# input5.net
KiCad netlist of a schematic drawn in Altium Designer
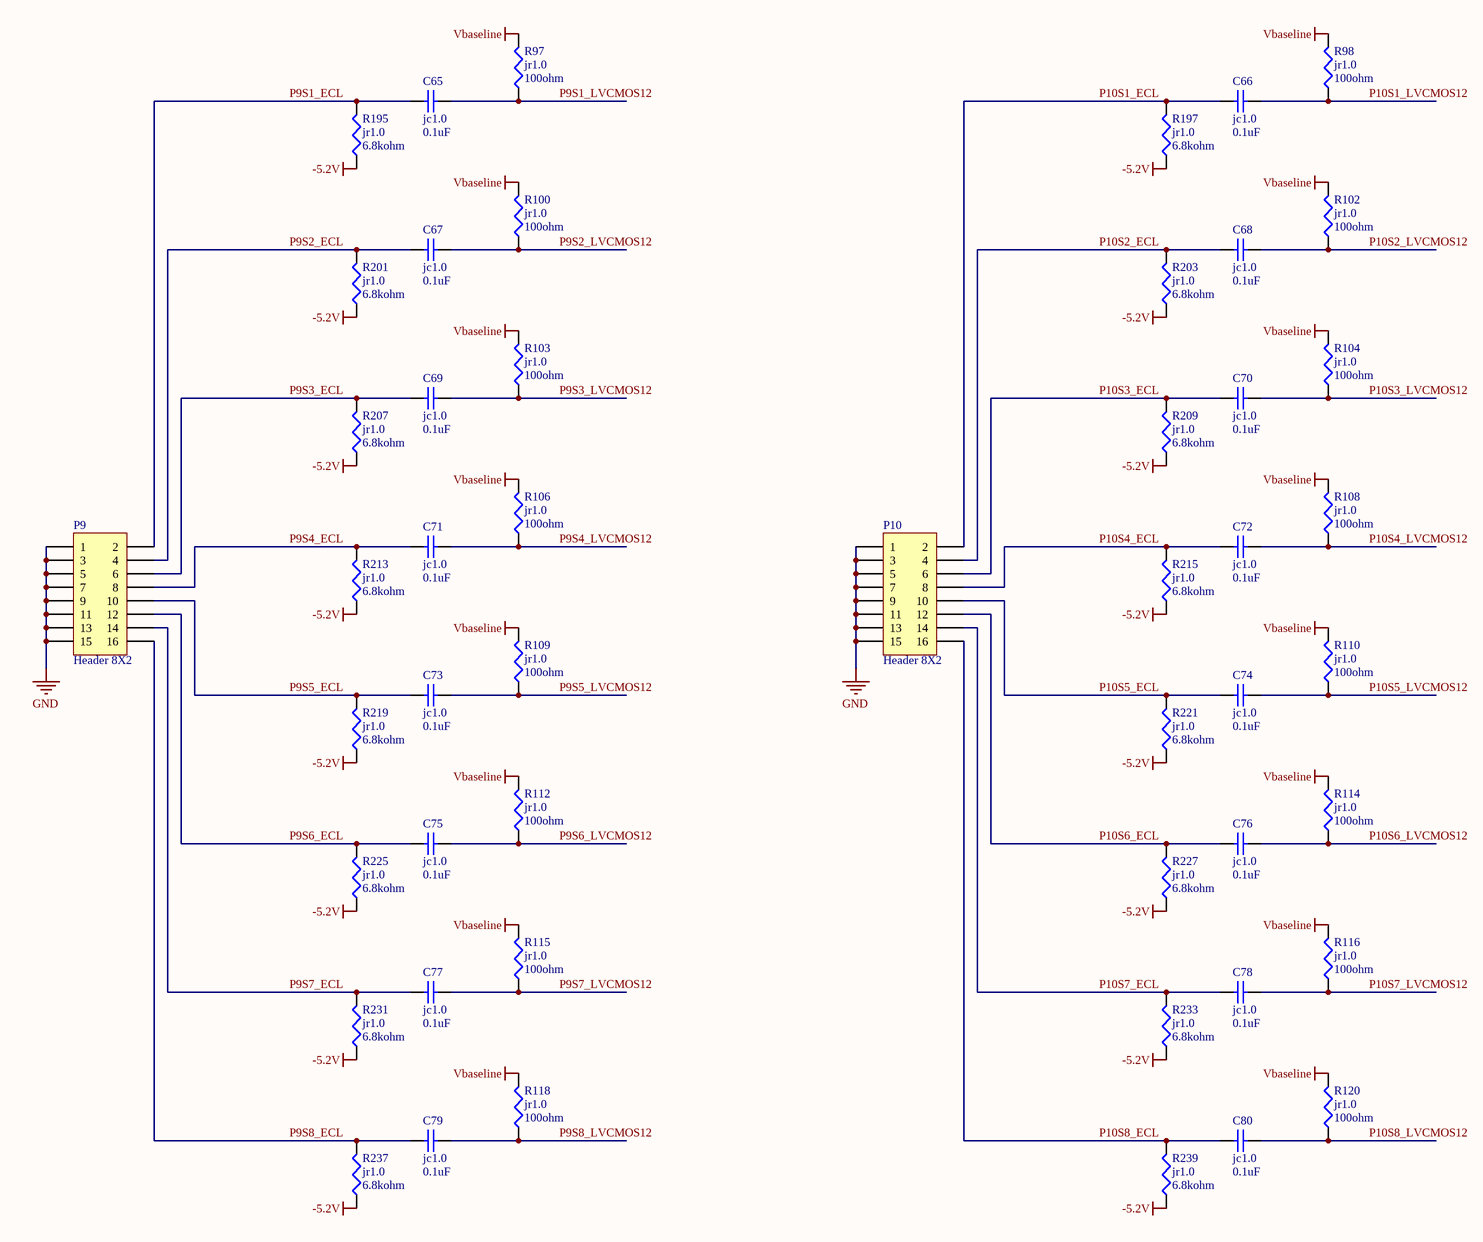
[diagram p0: input5.SchDoc]

(export (version "E")
  (design (tool "Eeschema 10.0.6"))
  (components
    (comp (ref "C65")
      (value "jc1.0")
      (footprint "0402")
      (description "Capacitor")
      (fields (field (name "ALTIUM_VALUE") "0.1uF") (field (name "PUBLISHER") "Altium Limited"))
      (libsource (lib "LIB01DXP2006SchLib") (part "Cap"))
    )
    (comp (ref "C66")
      (value "jc1.0")
      (footprint "0402")
      (description "Capacitor")
      (fields (field (name "ALTIUM_VALUE") "0.1uF") (field (name "PUBLISHER") "Altium Limited"))
      (libsource (lib "LIB01DXP2006SchLib") (part "Cap"))
    )
    (comp (ref "C67")
      (value "jc1.0")
      (footprint "0402")
      (description "Capacitor")
      (fields (field (name "ALTIUM_VALUE") "0.1uF") (field (name "PUBLISHER") "Altium Limited"))
      (libsource (lib "LIB01DXP2006SchLib") (part "Cap"))
    )
    (comp (ref "C68")
      (value "jc1.0")
      (footprint "0402")
      (description "Capacitor")
      (fields (field (name "ALTIUM_VALUE") "0.1uF") (field (name "PUBLISHER") "Altium Limited"))
      (libsource (lib "LIB01DXP2006SchLib") (part "Cap"))
    )
    (comp (ref "C69")
      (value "jc1.0")
      (footprint "0402")
      (description "Capacitor")
      (fields (field (name "ALTIUM_VALUE") "0.1uF") (field (name "PUBLISHER") "Altium Limited"))
      (libsource (lib "LIB01DXP2006SchLib") (part "Cap"))
    )
    (comp (ref "C70")
      (value "jc1.0")
      (footprint "0402")
      (description "Capacitor")
      (fields (field (name "ALTIUM_VALUE") "0.1uF") (field (name "PUBLISHER") "Altium Limited"))
      (libsource (lib "LIB01DXP2006SchLib") (part "Cap"))
    )
    (comp (ref "C71")
      (value "jc1.0")
      (footprint "0402")
      (description "Capacitor")
      (fields (field (name "ALTIUM_VALUE") "0.1uF") (field (name "PUBLISHER") "Altium Limited"))
      (libsource (lib "LIB01DXP2006SchLib") (part "Cap"))
    )
    (comp (ref "C72")
      (value "jc1.0")
      (footprint "0402")
      (description "Capacitor")
      (fields (field (name "ALTIUM_VALUE") "0.1uF") (field (name "PUBLISHER") "Altium Limited"))
      (libsource (lib "LIB01DXP2006SchLib") (part "Cap"))
    )
    (comp (ref "C73")
      (value "jc1.0")
      (footprint "0402")
      (description "Capacitor")
      (fields (field (name "ALTIUM_VALUE") "0.1uF") (field (name "PUBLISHER") "Altium Limited"))
      (libsource (lib "LIB01DXP2006SchLib") (part "Cap"))
    )
    (comp (ref "C74")
      (value "jc1.0")
      (footprint "0402")
      (description "Capacitor")
      (fields (field (name "ALTIUM_VALUE") "0.1uF") (field (name "PUBLISHER") "Altium Limited"))
      (libsource (lib "LIB01DXP2006SchLib") (part "Cap"))
    )
    (comp (ref "C75")
      (value "jc1.0")
      (footprint "0402")
      (description "Capacitor")
      (fields (field (name "ALTIUM_VALUE") "0.1uF") (field (name "PUBLISHER") "Altium Limited"))
      (libsource (lib "LIB01DXP2006SchLib") (part "Cap"))
    )
    (comp (ref "C76")
      (value "jc1.0")
      (footprint "0402")
      (description "Capacitor")
      (fields (field (name "ALTIUM_VALUE") "0.1uF") (field (name "PUBLISHER") "Altium Limited"))
      (libsource (lib "LIB01DXP2006SchLib") (part "Cap"))
    )
    (comp (ref "C77")
      (value "jc1.0")
      (footprint "0402")
      (description "Capacitor")
      (fields (field (name "ALTIUM_VALUE") "0.1uF") (field (name "PUBLISHER") "Altium Limited"))
      (libsource (lib "LIB01DXP2006SchLib") (part "Cap"))
    )
    (comp (ref "C78")
      (value "jc1.0")
      (footprint "0402")
      (description "Capacitor")
      (fields (field (name "ALTIUM_VALUE") "0.1uF") (field (name "PUBLISHER") "Altium Limited"))
      (libsource (lib "LIB01DXP2006SchLib") (part "Cap"))
    )
    (comp (ref "C79")
      (value "jc1.0")
      (footprint "0402")
      (description "Capacitor")
      (fields (field (name "ALTIUM_VALUE") "0.1uF") (field (name "PUBLISHER") "Altium Limited"))
      (libsource (lib "LIB01DXP2006SchLib") (part "Cap"))
    )
    (comp (ref "C80")
      (value "jc1.0")
      (footprint "0402")
      (description "Capacitor")
      (fields (field (name "ALTIUM_VALUE") "0.1uF") (field (name "PUBLISHER") "Altium Limited"))
      (libsource (lib "LIB01DXP2006SchLib") (part "Cap"))
    )
    (comp (ref "P9")
      (value "Header 8X2")
      (footprint "HDR2X8")
      (description "Header, 8-Pin, Dual row")
      (fields (field (name "PUBLISHER") "Altium Limited"))
      (libsource (lib "Miscellaneous Connectors") (part "Header 8X2"))
    )
    (comp (ref "P10")
      (value "Header 8X2")
      (footprint "HDR2X8")
      (description "Header, 8-Pin, Dual row")
      (fields (field (name "PUBLISHER") "Altium Limited"))
      (libsource (lib "Miscellaneous Connectors") (part "Header 8X2"))
    )
    (comp (ref "R97")
      (value "jr1.0")
      (footprint "0402")
      (description "Resistor")
      (fields (field (name "ALTIUM_VALUE") "100ohm") (field (name "PUBLISHER") "Altium Limited"))
      (libsource (lib "LIB01DXP2006SchLib") (part "Res"))
    )
    (comp (ref "R98")
      (value "jr1.0")
      (footprint "0402")
      (description "Resistor")
      (fields (field (name "ALTIUM_VALUE") "100ohm") (field (name "PUBLISHER") "Altium Limited"))
      (libsource (lib "LIB01DXP2006SchLib") (part "Res"))
    )
    (comp (ref "R100")
      (value "jr1.0")
      (footprint "0402")
      (description "Resistor")
      (fields (field (name "ALTIUM_VALUE") "100ohm") (field (name "PUBLISHER") "Altium Limited"))
      (libsource (lib "LIB01DXP2006SchLib") (part "Res"))
    )
    (comp (ref "R102")
      (value "jr1.0")
      (footprint "0402")
      (description "Resistor")
      (fields (field (name "ALTIUM_VALUE") "100ohm") (field (name "PUBLISHER") "Altium Limited"))
      (libsource (lib "LIB01DXP2006SchLib") (part "Res"))
    )
    (comp (ref "R103")
      (value "jr1.0")
      (footprint "0402")
      (description "Resistor")
      (fields (field (name "ALTIUM_VALUE") "100ohm") (field (name "PUBLISHER") "Altium Limited"))
      (libsource (lib "LIB01DXP2006SchLib") (part "Res"))
    )
    (comp (ref "R104")
      (value "jr1.0")
      (footprint "0402")
      (description "Resistor")
      (fields (field (name "ALTIUM_VALUE") "100ohm") (field (name "PUBLISHER") "Altium Limited"))
      (libsource (lib "LIB01DXP2006SchLib") (part "Res"))
    )
    (comp (ref "R106")
      (value "jr1.0")
      (footprint "0402")
      (description "Resistor")
      (fields (field (name "ALTIUM_VALUE") "100ohm") (field (name "PUBLISHER") "Altium Limited"))
      (libsource (lib "LIB01DXP2006SchLib") (part "Res"))
    )
    (comp (ref "R108")
      (value "jr1.0")
      (footprint "0402")
      (description "Resistor")
      (fields (field (name "ALTIUM_VALUE") "100ohm") (field (name "PUBLISHER") "Altium Limited"))
      (libsource (lib "LIB01DXP2006SchLib") (part "Res"))
    )
    (comp (ref "R109")
      (value "jr1.0")
      (footprint "0402")
      (description "Resistor")
      (fields (field (name "ALTIUM_VALUE") "100ohm") (field (name "PUBLISHER") "Altium Limited"))
      (libsource (lib "LIB01DXP2006SchLib") (part "Res"))
    )
    (comp (ref "R110")
      (value "jr1.0")
      (footprint "0402")
      (description "Resistor")
      (fields (field (name "ALTIUM_VALUE") "100ohm") (field (name "PUBLISHER") "Altium Limited"))
      (libsource (lib "LIB01DXP2006SchLib") (part "Res"))
    )
    (comp (ref "R112")
      (value "jr1.0")
      (footprint "0402")
      (description "Resistor")
      (fields (field (name "ALTIUM_VALUE") "100ohm") (field (name "PUBLISHER") "Altium Limited"))
      (libsource (lib "LIB01DXP2006SchLib") (part "Res"))
    )
    (comp (ref "R114")
      (value "jr1.0")
      (footprint "0402")
      (description "Resistor")
      (fields (field (name "ALTIUM_VALUE") "100ohm") (field (name "PUBLISHER") "Altium Limited"))
      (libsource (lib "LIB01DXP2006SchLib") (part "Res"))
    )
    (comp (ref "R115")
      (value "jr1.0")
      (footprint "0402")
      (description "Resistor")
      (fields (field (name "ALTIUM_VALUE") "100ohm") (field (name "PUBLISHER") "Altium Limited"))
      (libsource (lib "LIB01DXP2006SchLib") (part "Res"))
    )
    (comp (ref "R116")
      (value "jr1.0")
      (footprint "0402")
      (description "Resistor")
      (fields (field (name "ALTIUM_VALUE") "100ohm") (field (name "PUBLISHER") "Altium Limited"))
      (libsource (lib "LIB01DXP2006SchLib") (part "Res"))
    )
    (comp (ref "R118")
      (value "jr1.0")
      (footprint "0402")
      (description "Resistor")
      (fields (field (name "ALTIUM_VALUE") "100ohm") (field (name "PUBLISHER") "Altium Limited"))
      (libsource (lib "LIB01DXP2006SchLib") (part "Res"))
    )
    (comp (ref "R120")
      (value "jr1.0")
      (footprint "0402")
      (description "Resistor")
      (fields (field (name "ALTIUM_VALUE") "100ohm") (field (name "PUBLISHER") "Altium Limited"))
      (libsource (lib "LIB01DXP2006SchLib") (part "Res"))
    )
    (comp (ref "R195")
      (value "jr1.0")
      (footprint "0402")
      (description "Resistor")
      (fields (field (name "ALTIUM_VALUE") "6.8kohm") (field (name "PUBLISHER") "Altium Limited"))
      (libsource (lib "LIB01DXP2006SchLib") (part "Res"))
    )
    (comp (ref "R197")
      (value "jr1.0")
      (footprint "0402")
      (description "Resistor")
      (fields (field (name "ALTIUM_VALUE") "6.8kohm") (field (name "PUBLISHER") "Altium Limited"))
      (libsource (lib "LIB01DXP2006SchLib") (part "Res"))
    )
    (comp (ref "R201")
      (value "jr1.0")
      (footprint "0402")
      (description "Resistor")
      (fields (field (name "ALTIUM_VALUE") "6.8kohm") (field (name "PUBLISHER") "Altium Limited"))
      (libsource (lib "LIB01DXP2006SchLib") (part "Res"))
    )
    (comp (ref "R203")
      (value "jr1.0")
      (footprint "0402")
      (description "Resistor")
      (fields (field (name "ALTIUM_VALUE") "6.8kohm") (field (name "PUBLISHER") "Altium Limited"))
      (libsource (lib "LIB01DXP2006SchLib") (part "Res"))
    )
    (comp (ref "R207")
      (value "jr1.0")
      (footprint "0402")
      (description "Resistor")
      (fields (field (name "ALTIUM_VALUE") "6.8kohm") (field (name "PUBLISHER") "Altium Limited"))
      (libsource (lib "LIB01DXP2006SchLib") (part "Res"))
    )
    (comp (ref "R209")
      (value "jr1.0")
      (footprint "0402")
      (description "Resistor")
      (fields (field (name "ALTIUM_VALUE") "6.8kohm") (field (name "PUBLISHER") "Altium Limited"))
      (libsource (lib "LIB01DXP2006SchLib") (part "Res"))
    )
    (comp (ref "R213")
      (value "jr1.0")
      (footprint "0402")
      (description "Resistor")
      (fields (field (name "ALTIUM_VALUE") "6.8kohm") (field (name "PUBLISHER") "Altium Limited"))
      (libsource (lib "LIB01DXP2006SchLib") (part "Res"))
    )
    (comp (ref "R215")
      (value "jr1.0")
      (footprint "0402")
      (description "Resistor")
      (fields (field (name "ALTIUM_VALUE") "6.8kohm") (field (name "PUBLISHER") "Altium Limited"))
      (libsource (lib "LIB01DXP2006SchLib") (part "Res"))
    )
    (comp (ref "R219")
      (value "jr1.0")
      (footprint "0402")
      (description "Resistor")
      (fields (field (name "ALTIUM_VALUE") "6.8kohm") (field (name "PUBLISHER") "Altium Limited"))
      (libsource (lib "LIB01DXP2006SchLib") (part "Res"))
    )
    (comp (ref "R221")
      (value "jr1.0")
      (footprint "0402")
      (description "Resistor")
      (fields (field (name "ALTIUM_VALUE") "6.8kohm") (field (name "PUBLISHER") "Altium Limited"))
      (libsource (lib "LIB01DXP2006SchLib") (part "Res"))
    )
    (comp (ref "R225")
      (value "jr1.0")
      (footprint "0402")
      (description "Resistor")
      (fields (field (name "ALTIUM_VALUE") "6.8kohm") (field (name "PUBLISHER") "Altium Limited"))
      (libsource (lib "LIB01DXP2006SchLib") (part "Res"))
    )
    (comp (ref "R227")
      (value "jr1.0")
      (footprint "0402")
      (description "Resistor")
      (fields (field (name "ALTIUM_VALUE") "6.8kohm") (field (name "PUBLISHER") "Altium Limited"))
      (libsource (lib "LIB01DXP2006SchLib") (part "Res"))
    )
    (comp (ref "R231")
      (value "jr1.0")
      (footprint "0402")
      (description "Resistor")
      (fields (field (name "ALTIUM_VALUE") "6.8kohm") (field (name "PUBLISHER") "Altium Limited"))
      (libsource (lib "LIB01DXP2006SchLib") (part "Res"))
    )
    (comp (ref "R233")
      (value "jr1.0")
      (footprint "0402")
      (description "Resistor")
      (fields (field (name "ALTIUM_VALUE") "6.8kohm") (field (name "PUBLISHER") "Altium Limited"))
      (libsource (lib "LIB01DXP2006SchLib") (part "Res"))
    )
    (comp (ref "R237")
      (value "jr1.0")
      (footprint "0402")
      (description "Resistor")
      (fields (field (name "ALTIUM_VALUE") "6.8kohm") (field (name "PUBLISHER") "Altium Limited"))
      (libsource (lib "LIB01DXP2006SchLib") (part "Res"))
    )
    (comp (ref "R239")
      (value "jr1.0")
      (footprint "0402")
      (description "Resistor")
      (fields (field (name "ALTIUM_VALUE") "6.8kohm") (field (name "PUBLISHER") "Altium Limited"))
      (libsource (lib "LIB01DXP2006SchLib") (part "Res"))
    )
  )
  (nets
    (net (code "1") (name "-5.2V") (class "Default")
      (node (ref "R195") (pin "1") (pinfunction "1_1") (pintype "passive"))
      (node (ref "R197") (pin "1") (pinfunction "1_1") (pintype "passive"))
      (node (ref "R201") (pin "1") (pinfunction "1_1") (pintype "passive"))
      (node (ref "R203") (pin "1") (pinfunction "1_1") (pintype "passive"))
      (node (ref "R207") (pin "1") (pinfunction "1_1") (pintype "passive"))
      (node (ref "R209") (pin "1") (pinfunction "1_1") (pintype "passive"))
      (node (ref "R213") (pin "1") (pinfunction "1_1") (pintype "passive"))
      (node (ref "R215") (pin "1") (pinfunction "1_1") (pintype "passive"))
      (node (ref "R219") (pin "1") (pinfunction "1_1") (pintype "passive"))
      (node (ref "R221") (pin "1") (pinfunction "1_1") (pintype "passive"))
      (node (ref "R225") (pin "1") (pinfunction "1_1") (pintype "passive"))
      (node (ref "R227") (pin "1") (pinfunction "1_1") (pintype "passive"))
      (node (ref "R231") (pin "1") (pinfunction "1_1") (pintype "passive"))
      (node (ref "R233") (pin "1") (pinfunction "1_1") (pintype "passive"))
      (node (ref "R237") (pin "1") (pinfunction "1_1") (pintype "passive"))
      (node (ref "R239") (pin "1") (pinfunction "1_1") (pintype "passive"))
    )
    (net (code "2") (name "/P9S1_ECL") (class "Default")
      (node (ref "C65") (pin "1") (pinfunction "1_1") (pintype "passive"))
      (node (ref "P9") (pin "2") (pinfunction "2_2") (pintype "passive"))
      (node (ref "R195") (pin "2") (pinfunction "2_2") (pintype "passive"))
    )
    (net (code "3") (name "/P9S1_LVCMOS12") (class "Default")
      (node (ref "C65") (pin "2") (pinfunction "2_2") (pintype "passive"))
      (node (ref "R97") (pin "1") (pinfunction "1_1") (pintype "passive"))
    )
    (net (code "4") (name "/P9S2_ECL") (class "Default")
      (node (ref "C67") (pin "1") (pinfunction "1_1") (pintype "passive"))
      (node (ref "P9") (pin "4") (pinfunction "4_4") (pintype "passive"))
      (node (ref "R201") (pin "2") (pinfunction "2_2") (pintype "passive"))
    )
    (net (code "5") (name "/P9S2_LVCMOS12") (class "Default")
      (node (ref "C67") (pin "2") (pinfunction "2_2") (pintype "passive"))
      (node (ref "R100") (pin "1") (pinfunction "1_1") (pintype "passive"))
    )
    (net (code "6") (name "/P9S3_ECL") (class "Default")
      (node (ref "C69") (pin "1") (pinfunction "1_1") (pintype "passive"))
      (node (ref "P9") (pin "6") (pinfunction "6_6") (pintype "passive"))
      (node (ref "R207") (pin "2") (pinfunction "2_2") (pintype "passive"))
    )
    (net (code "7") (name "/P9S3_LVCMOS12") (class "Default")
      (node (ref "C69") (pin "2") (pinfunction "2_2") (pintype "passive"))
      (node (ref "R103") (pin "1") (pinfunction "1_1") (pintype "passive"))
    )
    (net (code "8") (name "/P9S4_ECL") (class "Default")
      (node (ref "C71") (pin "1") (pinfunction "1_1") (pintype "passive"))
      (node (ref "P9") (pin "8") (pinfunction "8_8") (pintype "passive"))
      (node (ref "R213") (pin "2") (pinfunction "2_2") (pintype "passive"))
    )
    (net (code "9") (name "/P9S4_LVCMOS12") (class "Default")
      (node (ref "C71") (pin "2") (pinfunction "2_2") (pintype "passive"))
      (node (ref "R106") (pin "1") (pinfunction "1_1") (pintype "passive"))
    )
    (net (code "10") (name "/P9S5_ECL") (class "Default")
      (node (ref "C73") (pin "1") (pinfunction "1_1") (pintype "passive"))
      (node (ref "P9") (pin "10") (pinfunction "10_10") (pintype "passive"))
      (node (ref "R219") (pin "2") (pinfunction "2_2") (pintype "passive"))
    )
    (net (code "11") (name "/P9S5_LVCMOS12") (class "Default")
      (node (ref "C73") (pin "2") (pinfunction "2_2") (pintype "passive"))
      (node (ref "R109") (pin "1") (pinfunction "1_1") (pintype "passive"))
    )
    (net (code "12") (name "/P9S6_ECL") (class "Default")
      (node (ref "C75") (pin "1") (pinfunction "1_1") (pintype "passive"))
      (node (ref "P9") (pin "12") (pinfunction "12_12") (pintype "passive"))
      (node (ref "R225") (pin "2") (pinfunction "2_2") (pintype "passive"))
    )
    (net (code "13") (name "/P9S6_LVCMOS12") (class "Default")
      (node (ref "C75") (pin "2") (pinfunction "2_2") (pintype "passive"))
      (node (ref "R112") (pin "1") (pinfunction "1_1") (pintype "passive"))
    )
    (net (code "14") (name "/P9S7_ECL") (class "Default")
      (node (ref "C77") (pin "1") (pinfunction "1_1") (pintype "passive"))
      (node (ref "P9") (pin "14") (pinfunction "14_14") (pintype "passive"))
      (node (ref "R231") (pin "2") (pinfunction "2_2") (pintype "passive"))
    )
    (net (code "15") (name "/P9S7_LVCMOS12") (class "Default")
      (node (ref "C77") (pin "2") (pinfunction "2_2") (pintype "passive"))
      (node (ref "R115") (pin "1") (pinfunction "1_1") (pintype "passive"))
    )
    (net (code "16") (name "/P9S8_ECL") (class "Default")
      (node (ref "C79") (pin "1") (pinfunction "1_1") (pintype "passive"))
      (node (ref "P9") (pin "16") (pinfunction "16_16") (pintype "passive"))
      (node (ref "R237") (pin "2") (pinfunction "2_2") (pintype "passive"))
    )
    (net (code "17") (name "/P9S8_LVCMOS12") (class "Default")
      (node (ref "C79") (pin "2") (pinfunction "2_2") (pintype "passive"))
      (node (ref "R118") (pin "1") (pinfunction "1_1") (pintype "passive"))
    )
    (net (code "18") (name "/P10S1_ECL") (class "Default")
      (node (ref "C66") (pin "1") (pinfunction "1_1") (pintype "passive"))
      (node (ref "P10") (pin "2") (pinfunction "2_2") (pintype "passive"))
      (node (ref "R197") (pin "2") (pinfunction "2_2") (pintype "passive"))
    )
    (net (code "19") (name "/P10S1_LVCMOS12") (class "Default")
      (node (ref "C66") (pin "2") (pinfunction "2_2") (pintype "passive"))
      (node (ref "R98") (pin "1") (pinfunction "1_1") (pintype "passive"))
    )
    (net (code "20") (name "/P10S2_ECL") (class "Default")
      (node (ref "C68") (pin "1") (pinfunction "1_1") (pintype "passive"))
      (node (ref "P10") (pin "4") (pinfunction "4_4") (pintype "passive"))
      (node (ref "R203") (pin "2") (pinfunction "2_2") (pintype "passive"))
    )
    (net (code "21") (name "/P10S2_LVCMOS12") (class "Default")
      (node (ref "C68") (pin "2") (pinfunction "2_2") (pintype "passive"))
      (node (ref "R102") (pin "1") (pinfunction "1_1") (pintype "passive"))
    )
    (net (code "22") (name "/P10S3_ECL") (class "Default")
      (node (ref "C70") (pin "1") (pinfunction "1_1") (pintype "passive"))
      (node (ref "P10") (pin "6") (pinfunction "6_6") (pintype "passive"))
      (node (ref "R209") (pin "2") (pinfunction "2_2") (pintype "passive"))
    )
    (net (code "23") (name "/P10S3_LVCMOS12") (class "Default")
      (node (ref "C70") (pin "2") (pinfunction "2_2") (pintype "passive"))
      (node (ref "R104") (pin "1") (pinfunction "1_1") (pintype "passive"))
    )
    (net (code "24") (name "/P10S4_ECL") (class "Default")
      (node (ref "C72") (pin "1") (pinfunction "1_1") (pintype "passive"))
      (node (ref "P10") (pin "8") (pinfunction "8_8") (pintype "passive"))
      (node (ref "R215") (pin "2") (pinfunction "2_2") (pintype "passive"))
    )
    (net (code "25") (name "/P10S4_LVCMOS12") (class "Default")
      (node (ref "C72") (pin "2") (pinfunction "2_2") (pintype "passive"))
      (node (ref "R108") (pin "1") (pinfunction "1_1") (pintype "passive"))
    )
    (net (code "26") (name "/P10S5_ECL") (class "Default")
      (node (ref "C74") (pin "1") (pinfunction "1_1") (pintype "passive"))
      (node (ref "P10") (pin "10") (pinfunction "10_10") (pintype "passive"))
      (node (ref "R221") (pin "2") (pinfunction "2_2") (pintype "passive"))
    )
    (net (code "27") (name "/P10S5_LVCMOS12") (class "Default")
      (node (ref "C74") (pin "2") (pinfunction "2_2") (pintype "passive"))
      (node (ref "R110") (pin "1") (pinfunction "1_1") (pintype "passive"))
    )
    (net (code "28") (name "/P10S6_ECL") (class "Default")
      (node (ref "C76") (pin "1") (pinfunction "1_1") (pintype "passive"))
      (node (ref "P10") (pin "12") (pinfunction "12_12") (pintype "passive"))
      (node (ref "R227") (pin "2") (pinfunction "2_2") (pintype "passive"))
    )
    (net (code "29") (name "/P10S6_LVCMOS12") (class "Default")
      (node (ref "C76") (pin "2") (pinfunction "2_2") (pintype "passive"))
      (node (ref "R114") (pin "1") (pinfunction "1_1") (pintype "passive"))
    )
    (net (code "30") (name "/P10S7_ECL") (class "Default")
      (node (ref "C78") (pin "1") (pinfunction "1_1") (pintype "passive"))
      (node (ref "P10") (pin "14") (pinfunction "14_14") (pintype "passive"))
      (node (ref "R233") (pin "2") (pinfunction "2_2") (pintype "passive"))
    )
    (net (code "31") (name "/P10S7_LVCMOS12") (class "Default")
      (node (ref "C78") (pin "2") (pinfunction "2_2") (pintype "passive"))
      (node (ref "R116") (pin "1") (pinfunction "1_1") (pintype "passive"))
    )
    (net (code "32") (name "/P10S8_ECL") (class "Default")
      (node (ref "C80") (pin "1") (pinfunction "1_1") (pintype "passive"))
      (node (ref "P10") (pin "16") (pinfunction "16_16") (pintype "passive"))
      (node (ref "R239") (pin "2") (pinfunction "2_2") (pintype "passive"))
    )
    (net (code "33") (name "/P10S8_LVCMOS12") (class "Default")
      (node (ref "C80") (pin "2") (pinfunction "2_2") (pintype "passive"))
      (node (ref "R120") (pin "1") (pinfunction "1_1") (pintype "passive"))
    )
    (net (code "34") (name "GND") (class "Default")
      (node (ref "P10") (pin "1") (pinfunction "1_1") (pintype "passive"))
      (node (ref "P10") (pin "11") (pinfunction "11_11") (pintype "passive"))
      (node (ref "P10") (pin "13") (pinfunction "13_13") (pintype "passive"))
      (node (ref "P10") (pin "15") (pinfunction "15_15") (pintype "passive"))
      (node (ref "P10") (pin "3") (pinfunction "3_3") (pintype "passive"))
      (node (ref "P10") (pin "5") (pinfunction "5_5") (pintype "passive"))
      (node (ref "P10") (pin "7") (pinfunction "7_7") (pintype "passive"))
      (node (ref "P10") (pin "9") (pinfunction "9_9") (pintype "passive"))
      (node (ref "P9") (pin "1") (pinfunction "1_1") (pintype "passive"))
      (node (ref "P9") (pin "11") (pinfunction "11_11") (pintype "passive"))
      (node (ref "P9") (pin "13") (pinfunction "13_13") (pintype "passive"))
      (node (ref "P9") (pin "15") (pinfunction "15_15") (pintype "passive"))
      (node (ref "P9") (pin "3") (pinfunction "3_3") (pintype "passive"))
      (node (ref "P9") (pin "5") (pinfunction "5_5") (pintype "passive"))
      (node (ref "P9") (pin "7") (pinfunction "7_7") (pintype "passive"))
      (node (ref "P9") (pin "9") (pinfunction "9_9") (pintype "passive"))
    )
    (net (code "35") (name "Vbaseline") (class "Default")
      (node (ref "R100") (pin "2") (pinfunction "2_2") (pintype "passive"))
      (node (ref "R102") (pin "2") (pinfunction "2_2") (pintype "passive"))
      (node (ref "R103") (pin "2") (pinfunction "2_2") (pintype "passive"))
      (node (ref "R104") (pin "2") (pinfunction "2_2") (pintype "passive"))
      (node (ref "R106") (pin "2") (pinfunction "2_2") (pintype "passive"))
      (node (ref "R108") (pin "2") (pinfunction "2_2") (pintype "passive"))
      (node (ref "R109") (pin "2") (pinfunction "2_2") (pintype "passive"))
      (node (ref "R110") (pin "2") (pinfunction "2_2") (pintype "passive"))
      (node (ref "R112") (pin "2") (pinfunction "2_2") (pintype "passive"))
      (node (ref "R114") (pin "2") (pinfunction "2_2") (pintype "passive"))
      (node (ref "R115") (pin "2") (pinfunction "2_2") (pintype "passive"))
      (node (ref "R116") (pin "2") (pinfunction "2_2") (pintype "passive"))
      (node (ref "R118") (pin "2") (pinfunction "2_2") (pintype "passive"))
      (node (ref "R120") (pin "2") (pinfunction "2_2") (pintype "passive"))
      (node (ref "R97") (pin "2") (pinfunction "2_2") (pintype "passive"))
      (node (ref "R98") (pin "2") (pinfunction "2_2") (pintype "passive"))
    )
  )
)
